# Natcar_1_01.net
KiCad netlist of a schematic drawn in EAGLE
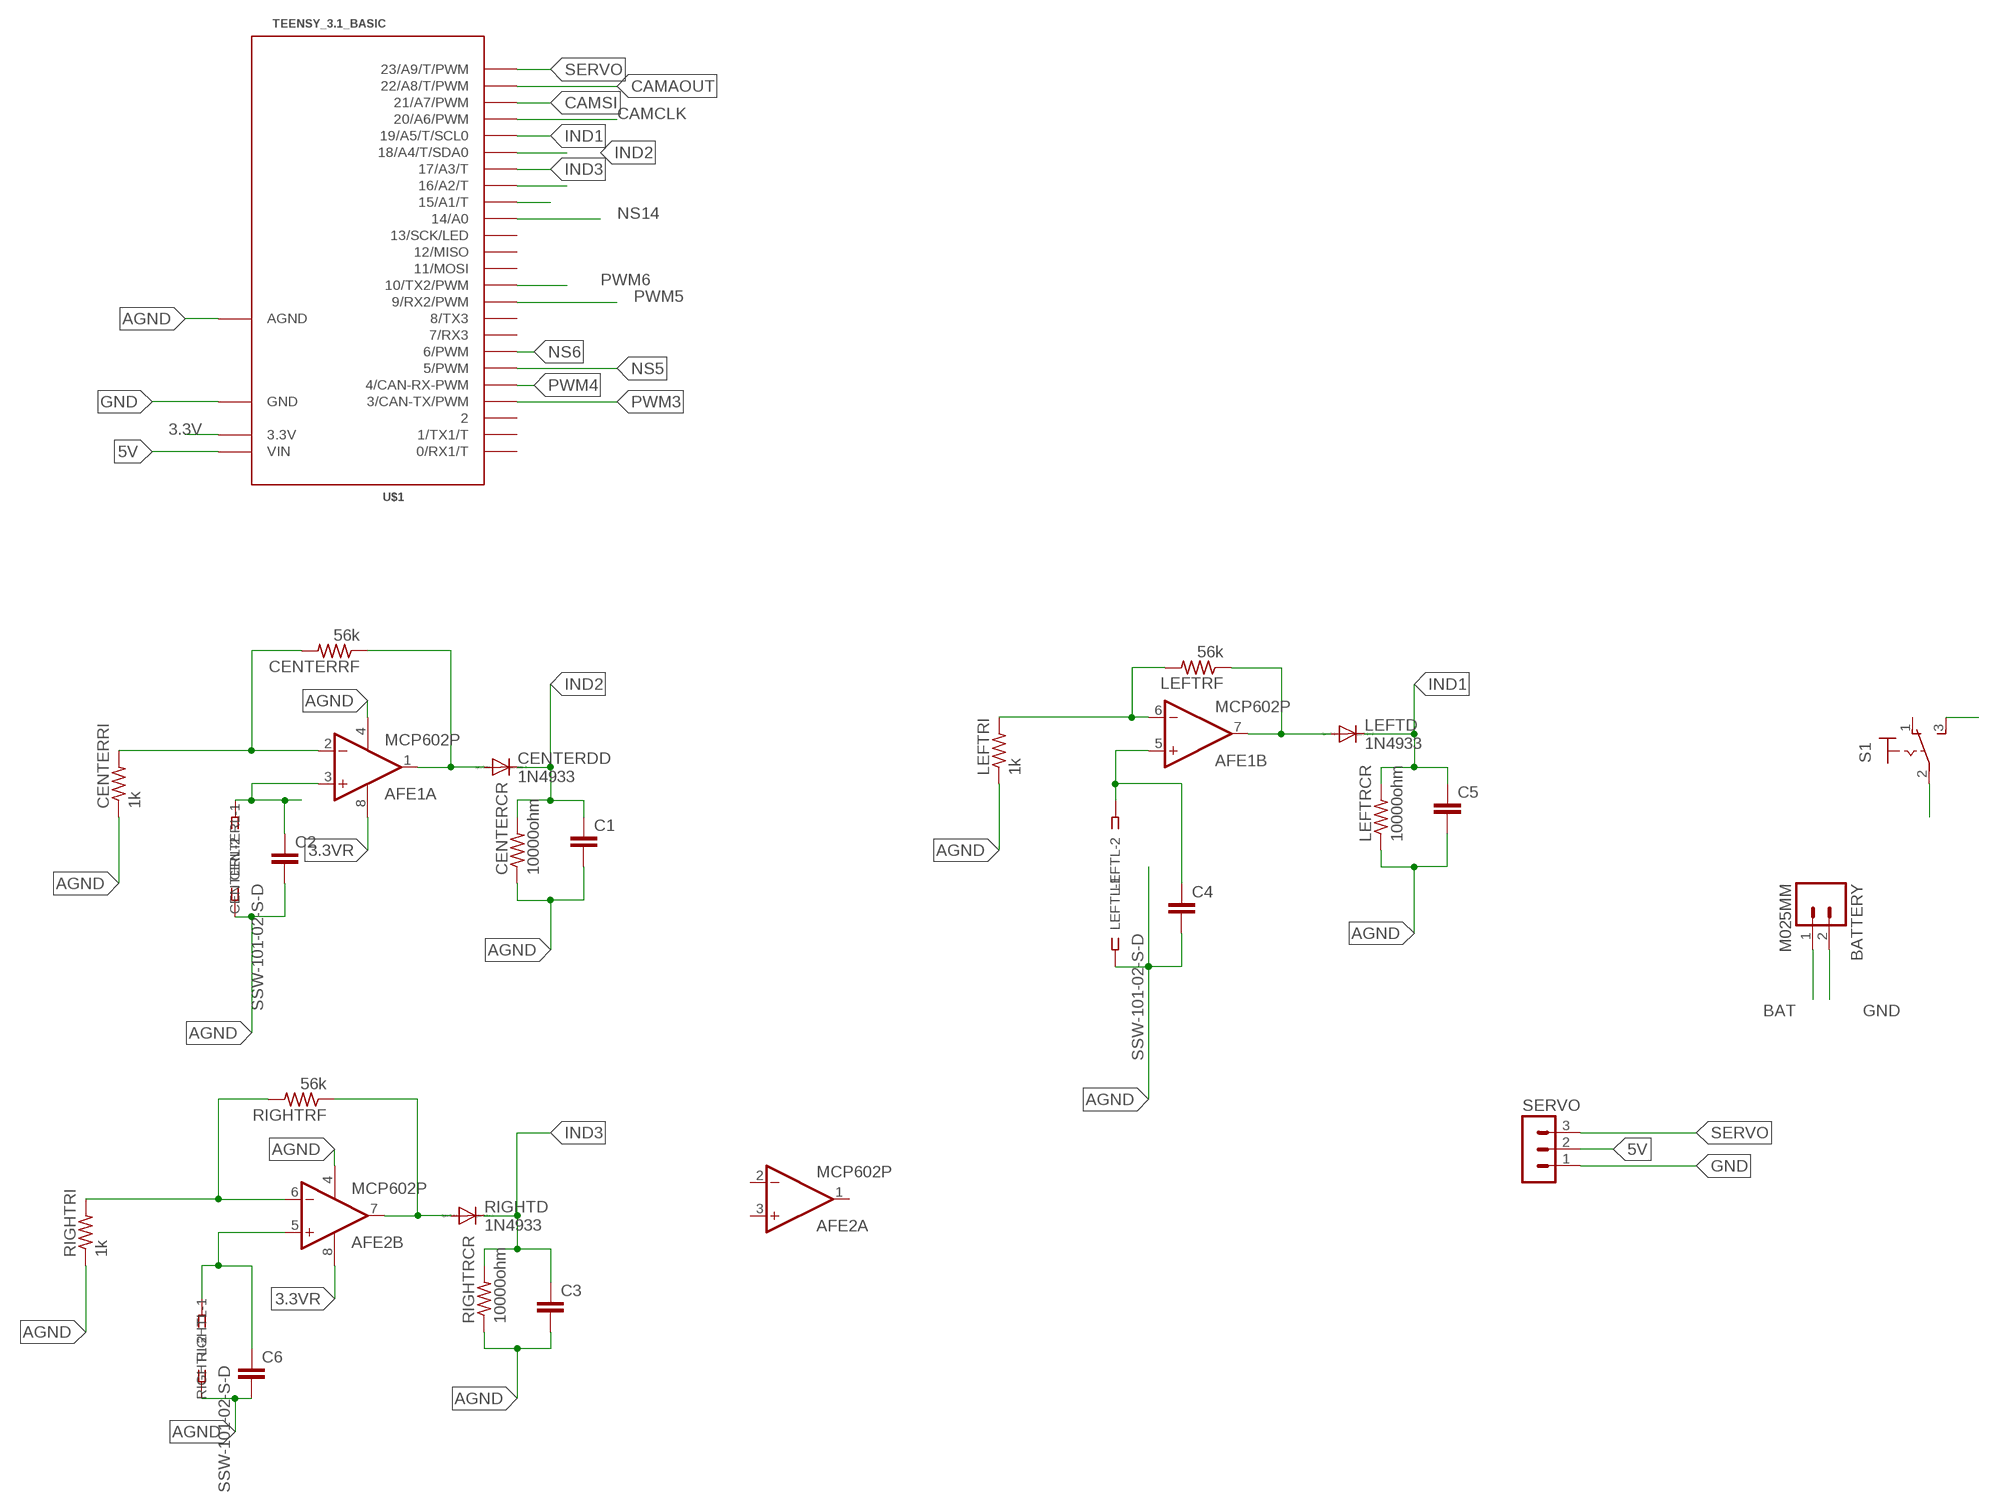
[diagram p0: schematic, sheet 1, part 1 of 2]
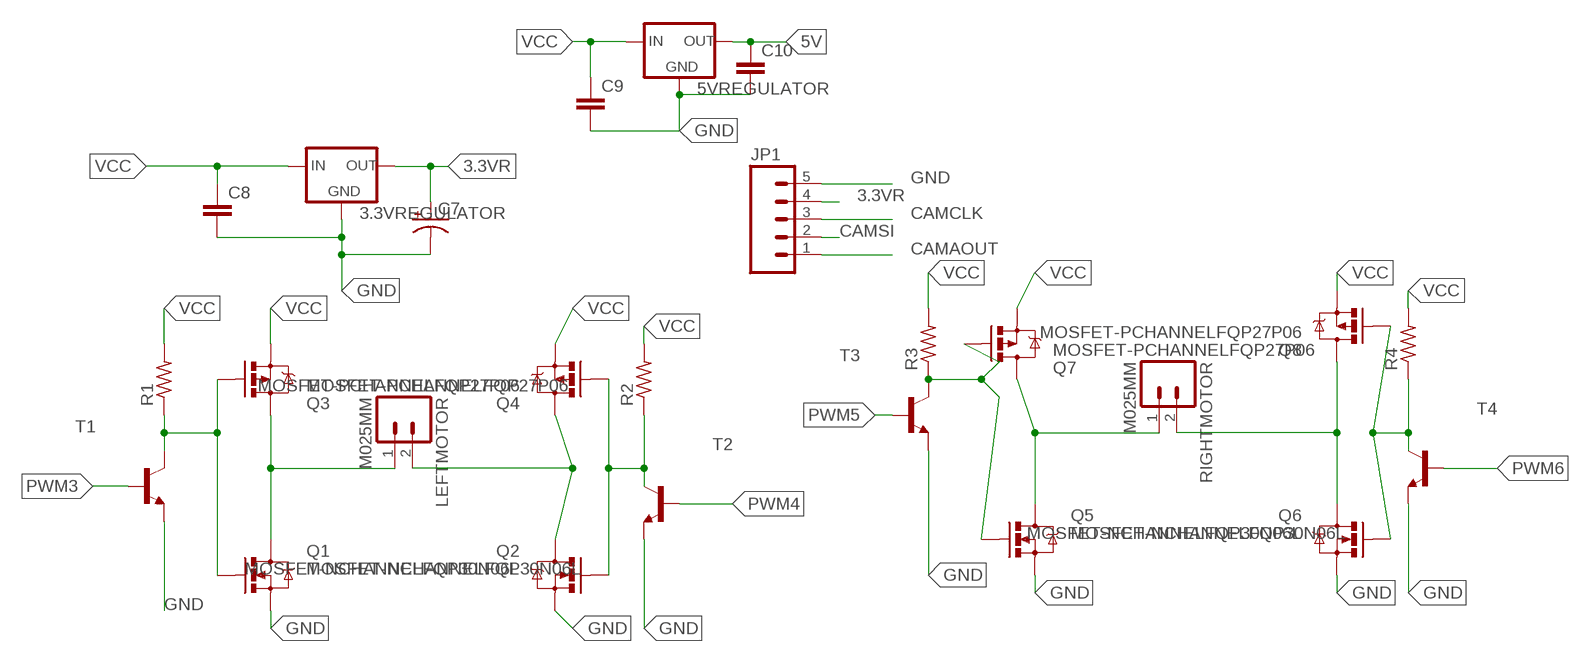
[diagram p1: schematic, sheet 1, part 2 of 2]

(export (version "E")
  (design (tool "Eeschema 10.0.6"))
  (components
    (comp (ref "3.3VREGULATOR")
      (value "V_REG_78XXSINK")
      (footprint "eagle-import:TO220-IGO")
      (libsource (lib "eagle-import") (part "V_REG_78XXSINK"))
    )
    (comp (ref "5VREGULATOR")
      (value "V_REG_78XXSINK")
      (footprint "eagle-import:TO220-IGO")
      (libsource (lib "eagle-import") (part "V_REG_78XXSINK"))
    )
    (comp (ref "AFE1")
      (value "MCP602P")
      (footprint "eagle-import:DIL08")
      (libsource (lib "eagle-import") (part "MCP602P"))
    )
    (comp (ref "AFE2")
      (value "MCP602P")
      (footprint "eagle-import:DIL08")
      (libsource (lib "eagle-import") (part "MCP602P"))
    )
    (comp (ref "BATTERY")
      (value "M025MM")
      (footprint "eagle-import:SCREWTERMINAL-5MM-2")
      (libsource (lib "eagle-import") (part "M025MM"))
    )
    (comp (ref "C1")
      (value "CAPEZ")
      (footprint "eagle-import:CAP-PTH-SMALLEZ")
      (libsource (lib "eagle-import") (part "CAPEZ"))
    )
    (comp (ref "C2")
      (value "CAPEZ")
      (footprint "eagle-import:CAP-PTH-SMALLEZ")
      (libsource (lib "eagle-import") (part "CAPEZ"))
    )
    (comp (ref "C3")
      (value "CAPEZ")
      (footprint "eagle-import:CAP-PTH-SMALLEZ")
      (libsource (lib "eagle-import") (part "CAPEZ"))
    )
    (comp (ref "C4")
      (value "CAPEZ")
      (footprint "eagle-import:CAP-PTH-SMALLEZ")
      (libsource (lib "eagle-import") (part "CAPEZ"))
    )
    (comp (ref "C5")
      (value "CAPEZ")
      (footprint "eagle-import:CAP-PTH-SMALLEZ")
      (libsource (lib "eagle-import") (part "CAPEZ"))
    )
    (comp (ref "C6")
      (value "CAPEZ")
      (footprint "eagle-import:CAP-PTH-SMALLEZ")
      (libsource (lib "eagle-import") (part "CAPEZ"))
    )
    (comp (ref "C7")
      (value "CAP_POLPTH2")
      (footprint "eagle-import:CPOL-RADIAL-10UF-25V")
      (libsource (lib "eagle-import") (part "CAP_POLPTH2"))
    )
    (comp (ref "C8")
      (value "CAPPTH2")
      (footprint "eagle-import:CAP-PTH-SMALL2")
      (libsource (lib "eagle-import") (part "CAPPTH2"))
    )
    (comp (ref "C9")
      (value "CAPPTH2")
      (footprint "eagle-import:CAP-PTH-SMALL2")
      (libsource (lib "eagle-import") (part "CAPPTH2"))
    )
    (comp (ref "C10")
      (value "CAPPTH2")
      (footprint "eagle-import:CAP-PTH-SMALL2")
      (libsource (lib "eagle-import") (part "CAPPTH2"))
    )
    (comp (ref "CENTERCR")
      (value "10000ohm")
      (footprint "eagle-import:0204_5")
      (libsource (lib "eagle-import") (part "R-US_0204/5"))
    )
    (comp (ref "CENTERDD")
      (value "1N4933")
      (footprint "eagle-import:DO41-10")
      (libsource (lib "eagle-import") (part "1N4933"))
    )
    (comp (ref "CENTERL")
      (value "SSW-101-02-S-D")
      (footprint "eagle-import:SSW-101-02-S-D")
      (libsource (lib "eagle-import") (part "SSW-101-02-S-D"))
    )
    (comp (ref "CENTERRF")
      (value "56k")
      (footprint "eagle-import:0204_5")
      (libsource (lib "eagle-import") (part "R-US_0204/5"))
    )
    (comp (ref "CENTERRI")
      (value "1k")
      (footprint "eagle-import:0204_5")
      (libsource (lib "eagle-import") (part "R-US_0204/5"))
    )
    (comp (ref "JP1")
      (value "M05PTH")
      (footprint "eagle-import:1X05")
      (libsource (lib "eagle-import") (part "M05PTH"))
    )
    (comp (ref "LEFTD")
      (value "1N4933")
      (footprint "eagle-import:DO41-10")
      (libsource (lib "eagle-import") (part "1N4933"))
    )
    (comp (ref "LEFTL")
      (value "SSW-101-02-S-D")
      (footprint "eagle-import:SSW-101-02-S-D")
      (libsource (lib "eagle-import") (part "SSW-101-02-S-D"))
    )
    (comp (ref "LEFTMOTOR")
      (value "M025MM")
      (footprint "eagle-import:SCREWTERMINAL-5MM-2")
      (libsource (lib "eagle-import") (part "M025MM"))
    )
    (comp (ref "LEFTRCR")
      (value "10000ohm")
      (footprint "eagle-import:0204_5")
      (libsource (lib "eagle-import") (part "R-US_0204/5"))
    )
    (comp (ref "LEFTRF")
      (value "56k")
      (footprint "eagle-import:0204_5")
      (libsource (lib "eagle-import") (part "R-US_0204/5"))
    )
    (comp (ref "LEFTRI")
      (value "1k")
      (footprint "eagle-import:0204_5")
      (libsource (lib "eagle-import") (part "R-US_0204/5"))
    )
    (comp (ref "Q1")
      (value "MOSFET-NCHANNELFQP30N06L")
      (footprint "eagle-import:TO220V")
      (libsource (lib "eagle-import") (part "MOSFET-NCHANNELFQP30N06L"))
    )
    (comp (ref "Q2")
      (value "MOSFET-NCHANNELFQP30N06L")
      (footprint "eagle-import:TO220V")
      (libsource (lib "eagle-import") (part "MOSFET-NCHANNELFQP30N06L"))
    )
    (comp (ref "Q3")
      (value "MOSFET-PCHANNELFQP27P06")
      (footprint "eagle-import:TO220V")
      (libsource (lib "eagle-import") (part "MOSFET-PCHANNELFQP27P06"))
    )
    (comp (ref "Q4")
      (value "MOSFET-PCHANNELFQP27P06")
      (footprint "eagle-import:TO220V")
      (libsource (lib "eagle-import") (part "MOSFET-PCHANNELFQP27P06"))
    )
    (comp (ref "Q5")
      (value "MOSFET-NCHANNELFQP30N06L")
      (footprint "eagle-import:TO220V")
      (libsource (lib "eagle-import") (part "MOSFET-NCHANNELFQP30N06L"))
    )
    (comp (ref "Q6")
      (value "MOSFET-NCHANNELFQP30N06L")
      (footprint "eagle-import:TO220V")
      (libsource (lib "eagle-import") (part "MOSFET-NCHANNELFQP30N06L"))
    )
    (comp (ref "Q7")
      (value "MOSFET-PCHANNELFQP27P06")
      (footprint "eagle-import:TO220V")
      (libsource (lib "eagle-import") (part "MOSFET-PCHANNELFQP27P06"))
    )
    (comp (ref "Q8")
      (value "MOSFET-PCHANNELFQP27P06")
      (footprint "eagle-import:TO220V")
      (libsource (lib "eagle-import") (part "MOSFET-PCHANNELFQP27P06"))
    )
    (comp (ref "R1")
      (value "R-US_0204/5")
      (footprint "eagle-import:0204_5")
      (libsource (lib "eagle-import") (part "R-US_0204/5"))
    )
    (comp (ref "R2")
      (value "R-US_0204/5")
      (footprint "eagle-import:0204_5")
      (libsource (lib "eagle-import") (part "R-US_0204/5"))
    )
    (comp (ref "R3")
      (value "R-US_0204/5")
      (footprint "eagle-import:0204_5")
      (libsource (lib "eagle-import") (part "R-US_0204/5"))
    )
    (comp (ref "R4")
      (value "R-US_0204/5")
      (footprint "eagle-import:0204_5")
      (libsource (lib "eagle-import") (part "R-US_0204/5"))
    )
    (comp (ref "RIGHTD")
      (value "1N4933")
      (footprint "eagle-import:DO41-10")
      (libsource (lib "eagle-import") (part "1N4933"))
    )
    (comp (ref "RIGHTL")
      (value "SSW-101-02-S-D")
      (footprint "eagle-import:SSW-101-02-S-D")
      (libsource (lib "eagle-import") (part "SSW-101-02-S-D"))
    )
    (comp (ref "RIGHTMOTOR")
      (value "M025MM")
      (footprint "eagle-import:SCREWTERMINAL-5MM-2")
      (libsource (lib "eagle-import") (part "M025MM"))
    )
    (comp (ref "RIGHTRCR")
      (value "10000ohm")
      (footprint "eagle-import:0204_5")
      (libsource (lib "eagle-import") (part "R-US_0204/5"))
    )
    (comp (ref "RIGHTRF")
      (value "56k")
      (footprint "eagle-import:0204_5")
      (libsource (lib "eagle-import") (part "R-US_0204/5"))
    )
    (comp (ref "RIGHTRI")
      (value "1k")
      (footprint "eagle-import:0204_5")
      (libsource (lib "eagle-import") (part "R-US_0204/5"))
    )
    (comp (ref "S1")
      (value "320-916")
      (footprint "eagle-import:320-916")
      (libsource (lib "eagle-import") (part "320-916"))
    )
    (comp (ref "SERVO")
      (value "MA03-1")
      (footprint "eagle-import:MA03-1")
      (libsource (lib "eagle-import") (part "MA03-1"))
    )
    (comp (ref "T1")
      (value "-NPN-TO92-EBC")
      (footprint "eagle-import:TO92-EBC")
      (libsource (lib "eagle-import") (part "-NPN-TO92-EBC"))
    )
    (comp (ref "T2")
      (value "-NPN-TO92-EBC")
      (footprint "eagle-import:TO92-EBC")
      (libsource (lib "eagle-import") (part "-NPN-TO92-EBC"))
    )
    (comp (ref "T3")
      (value "-NPN-TO92-EBC")
      (footprint "eagle-import:TO92-EBC")
      (libsource (lib "eagle-import") (part "-NPN-TO92-EBC"))
    )
    (comp (ref "T4")
      (value "-NPN-TO92-EBC")
      (footprint "eagle-import:TO92-EBC")
      (libsource (lib "eagle-import") (part "-NPN-TO92-EBC"))
    )
    (comp (ref "U$1")
      (value "TEENSY_3.1_BASIC")
      (footprint "eagle-import:TEENSY_3.1_BASIC")
      (libsource (lib "eagle-import") (part "TEENSY_3.1_BASIC"))
    )
  )
  (nets
    (net (code "1") (name "/3.3V") (class "Default")
      (node (ref "U$1") (pin "3.3V") (pinfunction "3.3V_3.3V") (pintype "power_in"))
    )
    (net (code "2") (name "/BAT") (class "Default")
      (node (ref "BATTERY") (pin "1") (pinfunction "1_1") (pintype "passive"))
      (node (ref "S1") (pin "3") (pinfunction "S_3") (pintype "passive"))
    )
    (net (code "3") (name "/CAMCLK") (class "Default")
      (node (ref "JP1") (pin "3") (pinfunction "3_3") (pintype "passive"))
      (node (ref "U$1") (pin "20/A6") (pinfunction "20/A6/PWM_20/A6") (pintype "bidirectional"))
    )
    (net (code "4") (name "/NS14") (class "Default")
      (node (ref "U$1") (pin "14/A0") (pinfunction "14/A0_14/A0") (pintype "bidirectional"))
    )
    (net (code "5") (name "3.3VR") (class "Default")
      (node (ref "3.3VREGULATOR") (pin "OUT") (pinfunction "OUT_OUT") (pintype "output"))
      (node (ref "AFE1") (pin "8") (pinfunction "V+_8") (pintype "power_in"))
      (node (ref "AFE2") (pin "8") (pinfunction "V+_8") (pintype "power_in"))
      (node (ref "C7") (pin "1") (pinfunction "+_1") (pintype "passive"))
      (node (ref "JP1") (pin "4") (pinfunction "4_4") (pintype "passive"))
    )
    (net (code "6") (name "5V") (class "Default")
      (node (ref "5VREGULATOR") (pin "OUT") (pinfunction "OUT_OUT") (pintype "output"))
      (node (ref "C10") (pin "1") (pinfunction "1_1") (pintype "passive"))
      (node (ref "SERVO") (pin "2") (pinfunction "2_2") (pintype "passive"))
      (node (ref "U$1") (pin "VIN") (pinfunction "VIN_VIN") (pintype "power_in"))
    )
    (net (code "7") (name "AGND") (class "Default")
      (node (ref "AFE1") (pin "4") (pinfunction "V-_4") (pintype "power_in"))
      (node (ref "AFE2") (pin "4") (pinfunction "V-_4") (pintype "power_in"))
      (node (ref "C1") (pin "2") (pinfunction "2_2") (pintype "passive"))
      (node (ref "C2") (pin "2") (pinfunction "2_2") (pintype "passive"))
      (node (ref "C3") (pin "2") (pinfunction "2_2") (pintype "passive"))
      (node (ref "C4") (pin "2") (pinfunction "2_2") (pintype "passive"))
      (node (ref "C5") (pin "2") (pinfunction "2_2") (pintype "passive"))
      (node (ref "C6") (pin "2") (pinfunction "2_2") (pintype "passive"))
      (node (ref "CENTERCR") (pin "1") (pinfunction "1_1") (pintype "passive"))
      (node (ref "CENTERL") (pin "1") (pinfunction "1_1") (pintype "passive"))
      (node (ref "CENTERRI") (pin "1") (pinfunction "1_1") (pintype "passive"))
      (node (ref "LEFTL") (pin "1") (pinfunction "1_1") (pintype "passive"))
      (node (ref "LEFTRCR") (pin "1") (pinfunction "1_1") (pintype "passive"))
      (node (ref "LEFTRI") (pin "1") (pinfunction "1_1") (pintype "passive"))
      (node (ref "RIGHTL") (pin "1") (pinfunction "1_1") (pintype "passive"))
      (node (ref "RIGHTRCR") (pin "1") (pinfunction "1_1") (pintype "passive"))
      (node (ref "RIGHTRI") (pin "1") (pinfunction "1_1") (pintype "passive"))
      (node (ref "U$1") (pin "AGND") (pinfunction "AGND_AGND") (pintype "power_in"))
    )
    (net (code "8") (name "CAMAOUT") (class "Default")
      (node (ref "JP1") (pin "1") (pinfunction "1_1") (pintype "passive"))
      (node (ref "U$1") (pin "22/A8") (pinfunction "22/A8/T/PWM_22/A8") (pintype "bidirectional"))
    )
    (net (code "9") (name "CAMSI") (class "Default")
      (node (ref "JP1") (pin "2") (pinfunction "2_2") (pintype "passive"))
      (node (ref "U$1") (pin "21/A7") (pinfunction "21/A7/PWM_21/A7") (pintype "bidirectional"))
    )
    (net (code "10") (name "GND") (class "Default")
      (node (ref "3.3VREGULATOR") (pin "GND") (pinfunction "GND_GND") (pintype "input"))
      (node (ref "5VREGULATOR") (pin "GND") (pinfunction "GND_GND") (pintype "input"))
      (node (ref "BATTERY") (pin "2") (pinfunction "2_2") (pintype "passive"))
      (node (ref "C10") (pin "2") (pinfunction "2_2") (pintype "passive"))
      (node (ref "C7") (pin "2") (pinfunction "-_2") (pintype "passive"))
      (node (ref "C8") (pin "2") (pinfunction "2_2") (pintype "passive"))
      (node (ref "C9") (pin "2") (pinfunction "2_2") (pintype "passive"))
      (node (ref "JP1") (pin "5") (pinfunction "5_5") (pintype "passive"))
      (node (ref "Q1") (pin "3") (pinfunction "S_3") (pintype "passive"))
      (node (ref "Q2") (pin "3") (pinfunction "S_3") (pintype "passive"))
      (node (ref "Q5") (pin "3") (pinfunction "S_3") (pintype "passive"))
      (node (ref "Q6") (pin "3") (pinfunction "S_3") (pintype "passive"))
      (node (ref "SERVO") (pin "1") (pinfunction "1_1") (pintype "passive"))
      (node (ref "T1") (pin "E") (pinfunction "E_E") (pintype "passive"))
      (node (ref "T2") (pin "E") (pinfunction "E_E") (pintype "passive"))
      (node (ref "T3") (pin "E") (pinfunction "E_E") (pintype "passive"))
      (node (ref "T4") (pin "E") (pinfunction "E_E") (pintype "passive"))
      (node (ref "U$1") (pin "GND") (pinfunction "GND_GND") (pintype "power_in"))
    )
    (net (code "11") (name "IND1") (class "Default")
      (node (ref "C5") (pin "1") (pinfunction "1_1") (pintype "passive"))
      (node (ref "LEFTD") (pin "C") (pinfunction "C_C") (pintype "passive"))
      (node (ref "LEFTRCR") (pin "2") (pinfunction "2_2") (pintype "passive"))
      (node (ref "U$1") (pin "19/A5") (pinfunction "19/A5/T/SCL0_19/A5") (pintype "bidirectional"))
    )
    (net (code "12") (name "IND2") (class "Default")
      (node (ref "C1") (pin "1") (pinfunction "1_1") (pintype "passive"))
      (node (ref "CENTERCR") (pin "2") (pinfunction "2_2") (pintype "passive"))
      (node (ref "CENTERDD") (pin "C") (pinfunction "C_C") (pintype "passive"))
      (node (ref "U$1") (pin "18/A4") (pinfunction "18/A4/T/SDA0_18/A4") (pintype "bidirectional"))
    )
    (net (code "13") (name "IND3") (class "Default")
      (node (ref "C3") (pin "1") (pinfunction "1_1") (pintype "passive"))
      (node (ref "RIGHTD") (pin "C") (pinfunction "C_C") (pintype "passive"))
      (node (ref "RIGHTRCR") (pin "2") (pinfunction "2_2") (pintype "passive"))
      (node (ref "U$1") (pin "17/A3") (pinfunction "17/A3/T_17/A3") (pintype "bidirectional"))
    )
    (net (code "14") (name "NS5") (class "Default")
      (node (ref "U$1") (pin "5") (pinfunction "5/PWM_5") (pintype "bidirectional"))
    )
    (net (code "15") (name "NS6") (class "Default")
      (node (ref "U$1") (pin "6") (pinfunction "6/PWM_6") (pintype "bidirectional"))
    )
    (net (code "16") (name "Net-(AFE1A-+IN)") (class "Default")
      (node (ref "AFE1") (pin "3") (pinfunction "+IN_3") (pintype "input"))
      (node (ref "C2") (pin "1") (pinfunction "1_1") (pintype "passive"))
      (node (ref "CENTERL") (pin "2") (pinfunction "1_2") (pintype "passive"))
    )
    (net (code "17") (name "Net-(AFE1A--IN)") (class "Default")
      (node (ref "AFE1") (pin "2") (pinfunction "-IN_2") (pintype "input"))
      (node (ref "CENTERRF") (pin "2") (pinfunction "2_2") (pintype "passive"))
      (node (ref "CENTERRI") (pin "2") (pinfunction "2_2") (pintype "passive"))
    )
    (net (code "18") (name "Net-(AFE1A-OUT)") (class "Default")
      (node (ref "AFE1") (pin "1") (pinfunction "OUT_1") (pintype "output"))
      (node (ref "CENTERDD") (pin "A") (pinfunction "A_A") (pintype "passive"))
      (node (ref "CENTERRF") (pin "1") (pinfunction "1_1") (pintype "passive"))
    )
    (net (code "19") (name "Net-(AFE1B-+IN)") (class "Default")
      (node (ref "AFE1") (pin "5") (pinfunction "+IN_5") (pintype "input"))
      (node (ref "C4") (pin "1") (pinfunction "1_1") (pintype "passive"))
      (node (ref "LEFTL") (pin "2") (pinfunction "1_2") (pintype "passive"))
    )
    (net (code "20") (name "Net-(AFE1B--IN)") (class "Default")
      (node (ref "AFE1") (pin "6") (pinfunction "-IN_6") (pintype "input"))
      (node (ref "LEFTRF") (pin "2") (pinfunction "2_2") (pintype "passive"))
      (node (ref "LEFTRI") (pin "2") (pinfunction "2_2") (pintype "passive"))
    )
    (net (code "21") (name "Net-(AFE1B-OUT)") (class "Default")
      (node (ref "AFE1") (pin "7") (pinfunction "OUT_7") (pintype "output"))
      (node (ref "LEFTD") (pin "A") (pinfunction "A_A") (pintype "passive"))
      (node (ref "LEFTRF") (pin "1") (pinfunction "1_1") (pintype "passive"))
    )
    (net (code "22") (name "Net-(AFE2B-+IN)") (class "Default")
      (node (ref "AFE2") (pin "5") (pinfunction "+IN_5") (pintype "input"))
      (node (ref "C6") (pin "1") (pinfunction "1_1") (pintype "passive"))
      (node (ref "RIGHTL") (pin "2") (pinfunction "1_2") (pintype "passive"))
    )
    (net (code "23") (name "Net-(AFE2B--IN)") (class "Default")
      (node (ref "AFE2") (pin "6") (pinfunction "-IN_6") (pintype "input"))
      (node (ref "RIGHTRF") (pin "2") (pinfunction "2_2") (pintype "passive"))
      (node (ref "RIGHTRI") (pin "2") (pinfunction "2_2") (pintype "passive"))
    )
    (net (code "24") (name "Net-(AFE2B-OUT)") (class "Default")
      (node (ref "AFE2") (pin "7") (pinfunction "OUT_7") (pintype "output"))
      (node (ref "RIGHTD") (pin "A") (pinfunction "A_A") (pintype "passive"))
      (node (ref "RIGHTRF") (pin "1") (pinfunction "1_1") (pintype "passive"))
    )
    (net (code "25") (name "Net-(Q1-D)") (class "Default")
      (node (ref "LEFTMOTOR") (pin "1") (pinfunction "1_1") (pintype "passive"))
      (node (ref "Q1") (pin "2") (pinfunction "D_2") (pintype "passive"))
      (node (ref "Q3") (pin "2") (pinfunction "D_2") (pintype "passive"))
    )
    (net (code "26") (name "Net-(Q1-G)") (class "Default")
      (node (ref "Q1") (pin "1") (pinfunction "G_1") (pintype "passive"))
      (node (ref "Q3") (pin "1") (pinfunction "G_1") (pintype "passive"))
      (node (ref "R1") (pin "1") (pinfunction "1_1") (pintype "passive"))
      (node (ref "T1") (pin "C") (pinfunction "C_C") (pintype "passive"))
    )
    (net (code "27") (name "Net-(Q2-D)") (class "Default")
      (node (ref "LEFTMOTOR") (pin "2") (pinfunction "2_2") (pintype "passive"))
      (node (ref "Q2") (pin "2") (pinfunction "D_2") (pintype "passive"))
      (node (ref "Q4") (pin "2") (pinfunction "D_2") (pintype "passive"))
    )
    (net (code "28") (name "Net-(Q2-G)") (class "Default")
      (node (ref "Q2") (pin "1") (pinfunction "G_1") (pintype "passive"))
      (node (ref "Q4") (pin "1") (pinfunction "G_1") (pintype "passive"))
      (node (ref "R2") (pin "1") (pinfunction "1_1") (pintype "passive"))
      (node (ref "T2") (pin "C") (pinfunction "C_C") (pintype "passive"))
    )
    (net (code "29") (name "Net-(Q5-D)") (class "Default")
      (node (ref "Q5") (pin "2") (pinfunction "D_2") (pintype "passive"))
      (node (ref "Q7") (pin "2") (pinfunction "D_2") (pintype "passive"))
      (node (ref "RIGHTMOTOR") (pin "1") (pinfunction "1_1") (pintype "passive"))
    )
    (net (code "30") (name "Net-(Q5-G)") (class "Default")
      (node (ref "Q5") (pin "1") (pinfunction "G_1") (pintype "passive"))
      (node (ref "Q7") (pin "1") (pinfunction "G_1") (pintype "passive"))
      (node (ref "R3") (pin "1") (pinfunction "1_1") (pintype "passive"))
      (node (ref "T3") (pin "C") (pinfunction "C_C") (pintype "passive"))
    )
    (net (code "31") (name "Net-(Q6-D)") (class "Default")
      (node (ref "Q6") (pin "2") (pinfunction "D_2") (pintype "passive"))
      (node (ref "Q8") (pin "2") (pinfunction "D_2") (pintype "passive"))
      (node (ref "RIGHTMOTOR") (pin "2") (pinfunction "2_2") (pintype "passive"))
    )
    (net (code "32") (name "Net-(Q6-G)") (class "Default")
      (node (ref "Q6") (pin "1") (pinfunction "G_1") (pintype "passive"))
      (node (ref "Q8") (pin "1") (pinfunction "G_1") (pintype "passive"))
      (node (ref "R4") (pin "1") (pinfunction "1_1") (pintype "passive"))
      (node (ref "T4") (pin "C") (pinfunction "C_C") (pintype "passive"))
    )
    (net (code "33") (name "PWM3") (class "Default")
      (node (ref "T1") (pin "B") (pinfunction "B_B") (pintype "passive"))
      (node (ref "U$1") (pin "3") (pinfunction "3/CAN-TX/PWM_3") (pintype "bidirectional"))
    )
    (net (code "34") (name "PWM4") (class "Default")
      (node (ref "T2") (pin "B") (pinfunction "B_B") (pintype "passive"))
      (node (ref "U$1") (pin "4") (pinfunction "4/CAN-RX-PWM_4") (pintype "bidirectional"))
    )
    (net (code "35") (name "PWM5") (class "Default")
      (node (ref "T3") (pin "B") (pinfunction "B_B") (pintype "passive"))
      (node (ref "U$1") (pin "9") (pinfunction "9/RX2/PWM_9") (pintype "bidirectional"))
    )
    (net (code "36") (name "PWM6") (class "Default")
      (node (ref "T4") (pin "B") (pinfunction "B_B") (pintype "passive"))
      (node (ref "U$1") (pin "10") (pinfunction "10/TX2/PWM_10") (pintype "bidirectional"))
    )
    (net (code "37") (name "SERVO") (class "Default")
      (node (ref "SERVO") (pin "3") (pinfunction "3_3") (pintype "passive"))
      (node (ref "U$1") (pin "23/A9") (pinfunction "23/A9/T/PWM_23/A9") (pintype "bidirectional"))
    )
    (net (code "38") (name "VCC") (class "Default")
      (node (ref "3.3VREGULATOR") (pin "IN") (pinfunction "IN_IN") (pintype "input"))
      (node (ref "5VREGULATOR") (pin "IN") (pinfunction "IN_IN") (pintype "input"))
      (node (ref "C8") (pin "1") (pinfunction "1_1") (pintype "passive"))
      (node (ref "C9") (pin "1") (pinfunction "1_1") (pintype "passive"))
      (node (ref "Q3") (pin "3") (pinfunction "S_3") (pintype "passive"))
      (node (ref "Q4") (pin "3") (pinfunction "S_3") (pintype "passive"))
      (node (ref "Q7") (pin "3") (pinfunction "S_3") (pintype "passive"))
      (node (ref "Q8") (pin "3") (pinfunction "S_3") (pintype "passive"))
      (node (ref "R1") (pin "2") (pinfunction "2_2") (pintype "passive"))
      (node (ref "R2") (pin "2") (pinfunction "2_2") (pintype "passive"))
      (node (ref "R3") (pin "2") (pinfunction "2_2") (pintype "passive"))
      (node (ref "R4") (pin "2") (pinfunction "2_2") (pintype "passive"))
      (node (ref "S1") (pin "2") (pinfunction "P_2") (pintype "passive"))
    )
    (net (code "39") (name "unconnected-(AFE2A-+IN-Pad3)") (class "Default")
      (node (ref "AFE2") (pin "3") (pinfunction "+IN_3") (pintype "input"))
    )
    (net (code "40") (name "unconnected-(AFE2A--IN-Pad2)") (class "Default")
      (node (ref "AFE2") (pin "2") (pinfunction "-IN_2") (pintype "input"))
    )
    (net (code "41") (name "unconnected-(AFE2A-OUT-Pad1)") (class "Default")
      (node (ref "AFE2") (pin "1") (pinfunction "OUT_1") (pintype "output"))
    )
    (net (code "42") (name "unconnected-(S1-O-Pad1)") (class "Default")
      (node (ref "S1") (pin "1") (pinfunction "O_1") (pintype "passive"))
    )
    (net (code "43") (name "unconnected-(U$1-0{slash}RX1{slash}T-Pad0)") (class "Default")
      (node (ref "U$1") (pin "0") (pinfunction "0/RX1/T_0") (pintype "bidirectional"))
    )
    (net (code "44") (name "unconnected-(U$1-1{slash}TX1{slash}T-Pad1)") (class "Default")
      (node (ref "U$1") (pin "1") (pinfunction "1/TX1/T_1") (pintype "bidirectional"))
    )
    (net (code "45") (name "unconnected-(U$1-7{slash}RX3-Pad7)") (class "Default")
      (node (ref "U$1") (pin "7") (pinfunction "7/RX3_7") (pintype "bidirectional"))
    )
    (net (code "46") (name "unconnected-(U$1-8{slash}TX3-Pad8)") (class "Default")
      (node (ref "U$1") (pin "8") (pinfunction "8/TX3_8") (pintype "bidirectional"))
    )
    (net (code "47") (name "unconnected-(U$1-11{slash}MOSI-Pad11)") (class "Default")
      (node (ref "U$1") (pin "11") (pinfunction "11/MOSI_11") (pintype "bidirectional"))
    )
    (net (code "48") (name "unconnected-(U$1-12{slash}MISO-Pad12)") (class "Default")
      (node (ref "U$1") (pin "12") (pinfunction "12/MISO_12") (pintype "bidirectional"))
    )
    (net (code "49") (name "unconnected-(U$1-13{slash}SCK{slash}LED-Pad13)") (class "Default")
      (node (ref "U$1") (pin "13") (pinfunction "13/SCK/LED_13") (pintype "bidirectional"))
    )
    (net (code "50") (name "unconnected-(U$1-15{slash}A1{slash}T-Pad15{slash}A1)") (class "Default")
      (node (ref "U$1") (pin "15/A1") (pinfunction "15/A1/T_15/A1") (pintype "bidirectional"))
    )
    (net (code "51") (name "unconnected-(U$1-16{slash}A2{slash}T-Pad16{slash}A2)") (class "Default")
      (node (ref "U$1") (pin "16/A2") (pinfunction "16/A2/T_16/A2") (pintype "bidirectional"))
    )
    (net (code "52") (name "unconnected-(U$1-Pad2)") (class "Default")
      (node (ref "U$1") (pin "2") (pinfunction "2_2") (pintype "bidirectional"))
    )
  )
)
